# Sheet1.net
KiCad netlist of a schematic drawn in Altium Designer
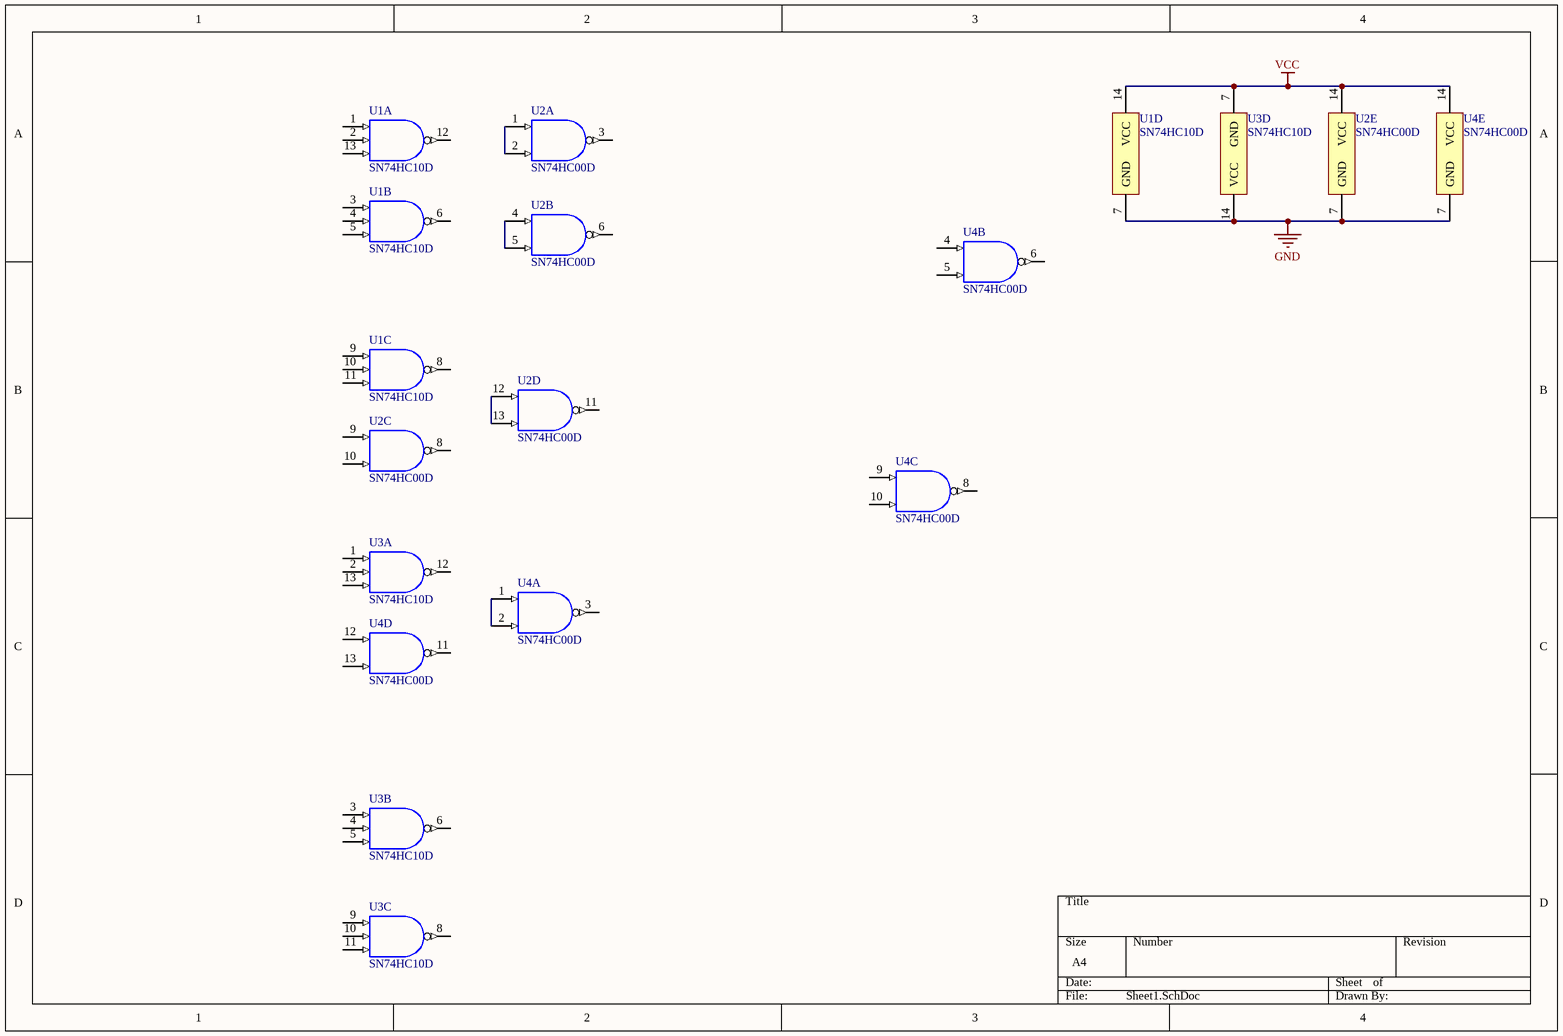
[diagram p0: Sheet1.SchDoc]

(export (version "E")
  (design (tool "Eeschema 10.0.6"))
  (components
    (comp (ref "U1")
      (value "SN74HC10D")
      (footprint "D0014A_M")
      (description "Triple 3-Input Positive-NAND Gates, D0014A, TUBE")
      (fields
        (field (name "MANUFACTURER") "Texas Instruments")
        (field (name "GENERIC PART NUMBER") "SN74HC10")
      )
      (libsource (lib "Altium Content Vault") (part "TI-SN74HC10-D0014A-14"))
    )
    (comp (ref "U2")
      (value "SN74HC00D")
      (footprint "D0014A_L")
      (description "Quad 2-Input Positive-NAND Gates, D0014A, TUBE")
      (fields
        (field (name "GENERIC PART NUMBER") "SN74HC00")
        (field (name "MANUFACTURER") "Texas Instruments")
      )
      (libsource (lib "Altium Content Vault") (part "TI-NAND-4-2IN-14_G"))
    )
    (comp (ref "U3")
      (value "SN74HC10D")
      (footprint "D0014A_M")
      (description "Triple 3-Input Positive-NAND Gates, D0014A, TUBE")
      (fields
        (field (name "MANUFACTURER") "Texas Instruments")
        (field (name "GENERIC PART NUMBER") "SN74HC10")
      )
      (libsource (lib "") (part "TI-SN74HC10-D0014A-14_1"))
    )
    (comp (ref "U4")
      (value "SN74HC00D")
      (footprint "D0014A_L")
      (description "Quad 2-Input Positive-NAND Gates, D0014A, TUBE")
      (fields
        (field (name "GENERIC PART NUMBER") "SN74HC00")
        (field (name "MANUFACTURER") "Texas Instruments")
      )
      (libsource (lib "") (part "TI-NAND-4-2IN-14_G_1"))
    )
  )
  (nets
    (net (code "1") (name "GND") (class "Default")
      (node (ref "U1") (pin "7") (pinfunction "GND_7") (pintype "power_in"))
      (node (ref "U2") (pin "7") (pinfunction "GND_7") (pintype "power_in"))
      (node (ref "U3") (pin "14") (pinfunction "VCC_14") (pintype "power_in"))
      (node (ref "U4") (pin "7") (pinfunction "GND_7") (pintype "power_in"))
    )
    (net (code "2") (name "Net-(U2A-1A)") (class "Default")
      (node (ref "U2") (pin "1") (pinfunction "1A_1") (pintype "input"))
      (node (ref "U2") (pin "2") (pinfunction "1B_2") (pintype "input"))
    )
    (net (code "3") (name "Net-(U2B-2A)") (class "Default")
      (node (ref "U2") (pin "4") (pinfunction "2A_4") (pintype "input"))
      (node (ref "U2") (pin "5") (pinfunction "2B_5") (pintype "input"))
    )
    (net (code "4") (name "Net-(U2D-4A)") (class "Default")
      (node (ref "U2") (pin "12") (pinfunction "4A_12") (pintype "input"))
      (node (ref "U2") (pin "13") (pinfunction "4B_13") (pintype "input"))
    )
    (net (code "5") (name "Net-(U4A-1A)") (class "Default")
      (node (ref "U4") (pin "1") (pinfunction "1A_1") (pintype "input"))
      (node (ref "U4") (pin "2") (pinfunction "1B_2") (pintype "input"))
    )
    (net (code "6") (name "VCC") (class "Default")
      (node (ref "U1") (pin "14") (pinfunction "VCC_14") (pintype "power_in"))
      (node (ref "U2") (pin "14") (pinfunction "VCC_14") (pintype "power_in"))
      (node (ref "U3") (pin "7") (pinfunction "GND_7") (pintype "power_in"))
      (node (ref "U4") (pin "14") (pinfunction "VCC_14") (pintype "power_in"))
    )
    (net (code "7") (name "unconnected-(U1A-1A-Pad1)") (class "Default")
      (node (ref "U1") (pin "1") (pinfunction "1A_1") (pintype "input"))
    )
    (net (code "8") (name "unconnected-(U1A-1B-Pad2)") (class "Default")
      (node (ref "U1") (pin "2") (pinfunction "1B_2") (pintype "input"))
    )
    (net (code "9") (name "unconnected-(U1A-1C-Pad13)") (class "Default")
      (node (ref "U1") (pin "13") (pinfunction "1C_13") (pintype "input"))
    )
    (net (code "10") (name "unconnected-(U1A-1Y-Pad12)") (class "Default")
      (node (ref "U1") (pin "12") (pinfunction "1Y_12") (pintype "output"))
    )
    (net (code "11") (name "unconnected-(U1B-2A-Pad3)") (class "Default")
      (node (ref "U1") (pin "3") (pinfunction "2A_3") (pintype "input"))
    )
    (net (code "12") (name "unconnected-(U1B-2B-Pad4)") (class "Default")
      (node (ref "U1") (pin "4") (pinfunction "2B_4") (pintype "input"))
    )
    (net (code "13") (name "unconnected-(U1B-2C-Pad5)") (class "Default")
      (node (ref "U1") (pin "5") (pinfunction "2C_5") (pintype "input"))
    )
    (net (code "14") (name "unconnected-(U1B-2Y-Pad6)") (class "Default")
      (node (ref "U1") (pin "6") (pinfunction "2Y_6") (pintype "output"))
    )
    (net (code "15") (name "unconnected-(U1C-3A-Pad9)") (class "Default")
      (node (ref "U1") (pin "9") (pinfunction "3A_9") (pintype "input"))
    )
    (net (code "16") (name "unconnected-(U1C-3B-Pad10)") (class "Default")
      (node (ref "U1") (pin "10") (pinfunction "3B_10") (pintype "input"))
    )
    (net (code "17") (name "unconnected-(U1C-3C-Pad11)") (class "Default")
      (node (ref "U1") (pin "11") (pinfunction "3C_11") (pintype "input"))
    )
    (net (code "18") (name "unconnected-(U1C-3Y-Pad8)") (class "Default")
      (node (ref "U1") (pin "8") (pinfunction "3Y_8") (pintype "output"))
    )
    (net (code "19") (name "unconnected-(U2A-1Y-Pad3)") (class "Default")
      (node (ref "U2") (pin "3") (pinfunction "1Y_3") (pintype "output"))
    )
    (net (code "20") (name "unconnected-(U2B-2Y-Pad6)") (class "Default")
      (node (ref "U2") (pin "6") (pinfunction "2Y_6") (pintype "output"))
    )
    (net (code "21") (name "unconnected-(U2C-3A-Pad9)") (class "Default")
      (node (ref "U2") (pin "9") (pinfunction "3A_9") (pintype "input"))
    )
    (net (code "22") (name "unconnected-(U2C-3B-Pad10)") (class "Default")
      (node (ref "U2") (pin "10") (pinfunction "3B_10") (pintype "input"))
    )
    (net (code "23") (name "unconnected-(U2C-3Y-Pad8)") (class "Default")
      (node (ref "U2") (pin "8") (pinfunction "3Y_8") (pintype "output"))
    )
    (net (code "24") (name "unconnected-(U2D-4Y-Pad11)") (class "Default")
      (node (ref "U2") (pin "11") (pinfunction "4Y_11") (pintype "output"))
    )
    (net (code "25") (name "unconnected-(U3A-1A-Pad1)") (class "Default")
      (node (ref "U3") (pin "1") (pinfunction "1A_1") (pintype "input"))
    )
    (net (code "26") (name "unconnected-(U3A-1B-Pad2)") (class "Default")
      (node (ref "U3") (pin "2") (pinfunction "1B_2") (pintype "input"))
    )
    (net (code "27") (name "unconnected-(U3A-1C-Pad13)") (class "Default")
      (node (ref "U3") (pin "13") (pinfunction "1C_13") (pintype "input"))
    )
    (net (code "28") (name "unconnected-(U3A-1Y-Pad12)") (class "Default")
      (node (ref "U3") (pin "12") (pinfunction "1Y_12") (pintype "output"))
    )
    (net (code "29") (name "unconnected-(U3B-2A-Pad3)") (class "Default")
      (node (ref "U3") (pin "3") (pinfunction "2A_3") (pintype "input"))
    )
    (net (code "30") (name "unconnected-(U3B-2B-Pad4)") (class "Default")
      (node (ref "U3") (pin "4") (pinfunction "2B_4") (pintype "input"))
    )
    (net (code "31") (name "unconnected-(U3B-2C-Pad5)") (class "Default")
      (node (ref "U3") (pin "5") (pinfunction "2C_5") (pintype "input"))
    )
    (net (code "32") (name "unconnected-(U3B-2Y-Pad6)") (class "Default")
      (node (ref "U3") (pin "6") (pinfunction "2Y_6") (pintype "output"))
    )
    (net (code "33") (name "unconnected-(U3C-3A-Pad9)") (class "Default")
      (node (ref "U3") (pin "9") (pinfunction "3A_9") (pintype "input"))
    )
    (net (code "34") (name "unconnected-(U3C-3B-Pad10)") (class "Default")
      (node (ref "U3") (pin "10") (pinfunction "3B_10") (pintype "input"))
    )
    (net (code "35") (name "unconnected-(U3C-3C-Pad11)") (class "Default")
      (node (ref "U3") (pin "11") (pinfunction "3C_11") (pintype "input"))
    )
    (net (code "36") (name "unconnected-(U3C-3Y-Pad8)") (class "Default")
      (node (ref "U3") (pin "8") (pinfunction "3Y_8") (pintype "output"))
    )
    (net (code "37") (name "unconnected-(U4A-1Y-Pad3)") (class "Default")
      (node (ref "U4") (pin "3") (pinfunction "1Y_3") (pintype "output"))
    )
    (net (code "38") (name "unconnected-(U4B-2A-Pad4)") (class "Default")
      (node (ref "U4") (pin "4") (pinfunction "2A_4") (pintype "input"))
    )
    (net (code "39") (name "unconnected-(U4B-2B-Pad5)") (class "Default")
      (node (ref "U4") (pin "5") (pinfunction "2B_5") (pintype "input"))
    )
    (net (code "40") (name "unconnected-(U4B-2Y-Pad6)") (class "Default")
      (node (ref "U4") (pin "6") (pinfunction "2Y_6") (pintype "output"))
    )
    (net (code "41") (name "unconnected-(U4C-3A-Pad9)") (class "Default")
      (node (ref "U4") (pin "9") (pinfunction "3A_9") (pintype "input"))
    )
    (net (code "42") (name "unconnected-(U4C-3B-Pad10)") (class "Default")
      (node (ref "U4") (pin "10") (pinfunction "3B_10") (pintype "input"))
    )
    (net (code "43") (name "unconnected-(U4C-3Y-Pad8)") (class "Default")
      (node (ref "U4") (pin "8") (pinfunction "3Y_8") (pintype "output"))
    )
    (net (code "44") (name "unconnected-(U4D-4A-Pad12)") (class "Default")
      (node (ref "U4") (pin "12") (pinfunction "4A_12") (pintype "input"))
    )
    (net (code "45") (name "unconnected-(U4D-4B-Pad13)") (class "Default")
      (node (ref "U4") (pin "13") (pinfunction "4B_13") (pintype "input"))
    )
    (net (code "46") (name "unconnected-(U4D-4Y-Pad11)") (class "Default")
      (node (ref "U4") (pin "11") (pinfunction "4Y_11") (pintype "output"))
    )
  )
)
